# motorline.net
KiCad netlist of a schematic drawn in EAGLE
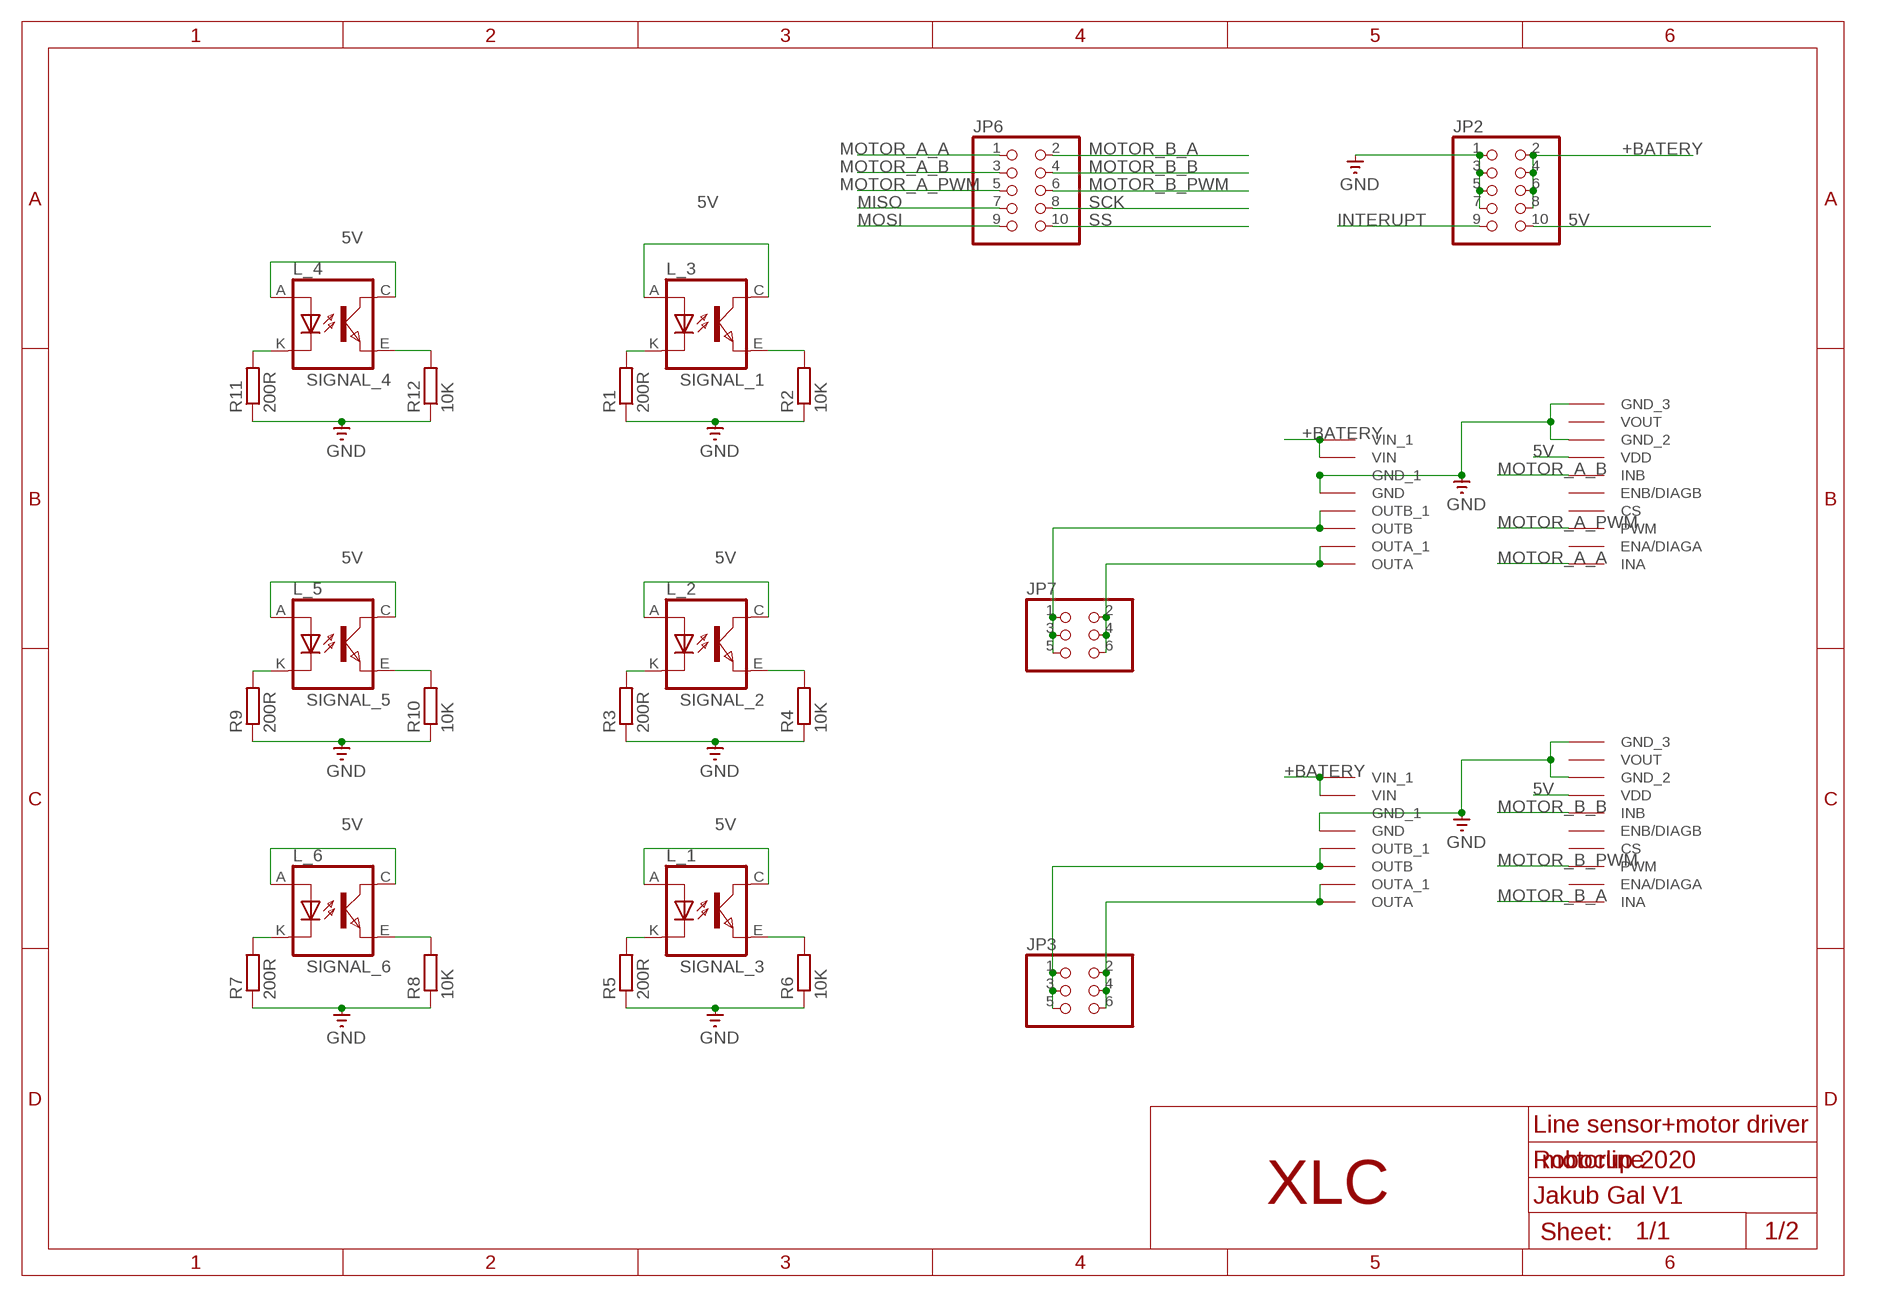
[diagram p0: schematic, sheet 1, part 1 of 2]
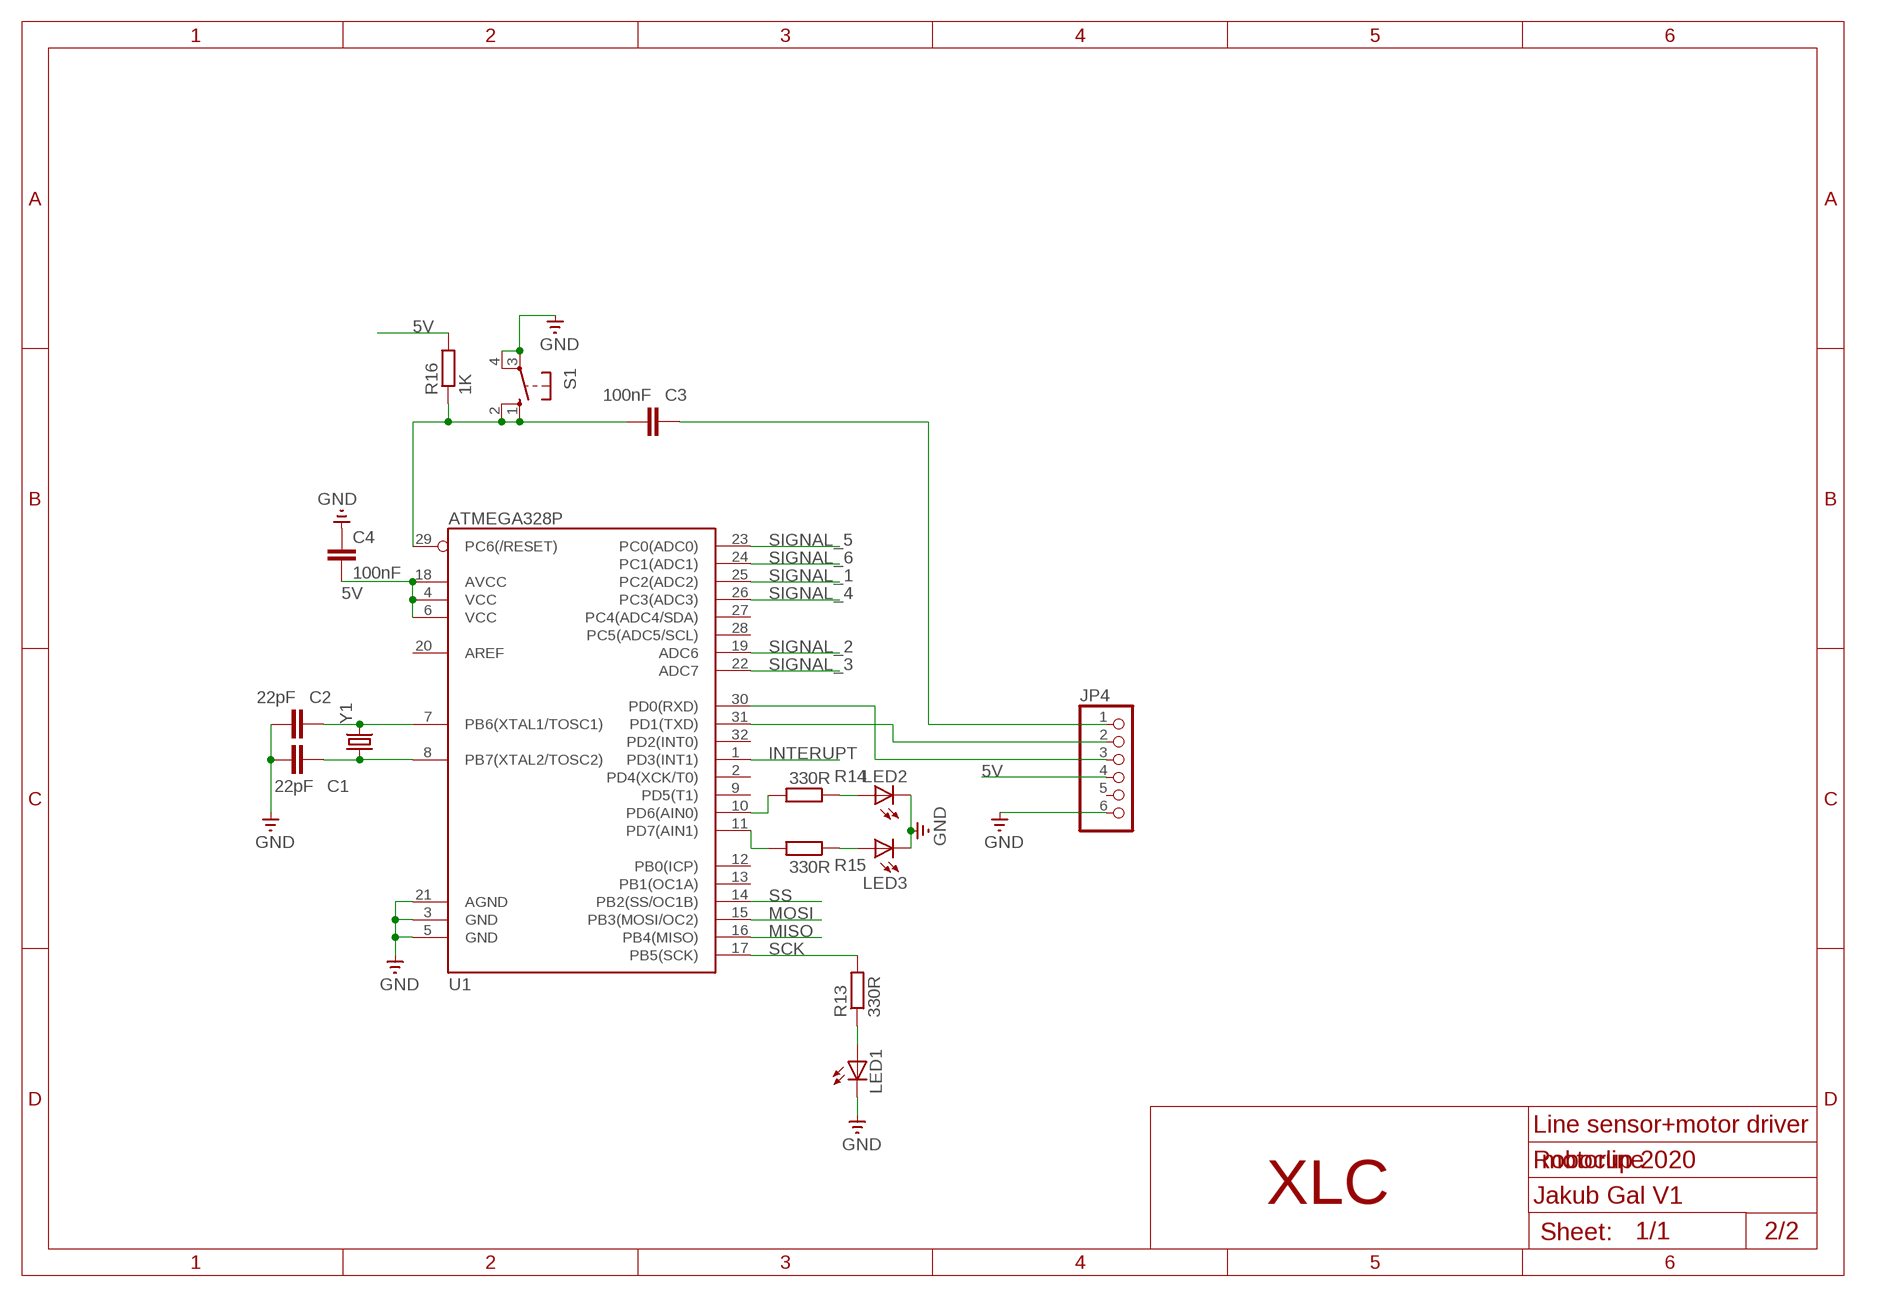
[diagram p1: schematic, sheet 1, part 2 of 2]

(export (version "E")
  (design (tool "Eeschema 10.0.6"))
  (components
    (comp (ref "C1")
      (value "22pF")
      (footprint "eagle-import:C0603")
      (libsource (lib "eagle-import") (part "C-EUC0603"))
    )
    (comp (ref "C2")
      (value "22pF")
      (footprint "eagle-import:C0603")
      (libsource (lib "eagle-import") (part "C-EUC0603"))
    )
    (comp (ref "C3")
      (value "100nF")
      (footprint "eagle-import:C0603")
      (libsource (lib "eagle-import") (part "C-EUC0603"))
    )
    (comp (ref "C4")
      (value "100nF")
      (footprint "eagle-import:C0603")
      (libsource (lib "eagle-import") (part "rcl_334_C-EUC0603"))
    )
    (comp (ref "JP2")
      (value "PINHD-2X5IDC")
      (footprint "eagle-import:2X05_IDC")
      (libsource (lib "eagle-import") (part "PINHD-2X5IDC"))
    )
    (comp (ref "JP3")
      (value "PINHD-2X3IDC")
      (footprint "eagle-import:2X03_IDC")
      (libsource (lib "eagle-import") (part "PINHD-2X3IDC"))
    )
    (comp (ref "JP4")
      (value "PINHD-1X6_2.54-90°")
      (footprint "eagle-import:1X06_90")
      (libsource (lib "eagle-import") (part "PINHD-1X6_2.54-90°"))
    )
    (comp (ref "JP6")
      (value "PINHD-2X5IDC")
      (footprint "eagle-import:2X05_IDC")
      (libsource (lib "eagle-import") (part "PINHD-2X5IDC"))
    )
    (comp (ref "JP7")
      (value "PINHD-2X3IDC")
      (footprint "eagle-import:2X03_IDC")
      (libsource (lib "eagle-import") (part "PINHD-2X3IDC"))
    )
    (comp (ref "LED1")
      (value "LEDCHIPLED_0603")
      (footprint "eagle-import:CHIPLED_0603")
      (libsource (lib "eagle-import") (part "LEDCHIPLED_0603"))
    )
    (comp (ref "LED2")
      (value "LEDCHIPLED_0603")
      (footprint "eagle-import:CHIPLED_0603")
      (libsource (lib "eagle-import") (part "LEDCHIPLED_0603"))
    )
    (comp (ref "LED3")
      (value "LEDCHIPLED_0603")
      (footprint "eagle-import:CHIPLED_0603")
      (libsource (lib "eagle-import") (part "LEDCHIPLED_0603"))
    )
    (comp (ref "L_1")
      (value "TCRT5000")
      (footprint "eagle-import:TCRT5000")
      (libsource (lib "eagle-import") (part "TCRT5000"))
    )
    (comp (ref "L_2")
      (value "TCRT5000")
      (footprint "eagle-import:TCRT5000")
      (libsource (lib "eagle-import") (part "TCRT5000"))
    )
    (comp (ref "L_3")
      (value "TCRT5000")
      (footprint "eagle-import:TCRT5000")
      (libsource (lib "eagle-import") (part "TCRT5000"))
    )
    (comp (ref "L_4")
      (value "TCRT5000")
      (footprint "eagle-import:TCRT5000")
      (fields (field (name "SPICEPREFIX") "O"))
      (libsource (lib "eagle-import") (part "TCRT5000"))
    )
    (comp (ref "L_5")
      (value "TCRT5000")
      (footprint "eagle-import:TCRT5000")
      (libsource (lib "eagle-import") (part "TCRT5000"))
    )
    (comp (ref "L_6")
      (value "TCRT5000")
      (footprint "eagle-import:TCRT5000")
      (fields (field (name "SPICEPREFIX") "O"))
      (libsource (lib "eagle-import") (part "TCRT5000"))
    )
    (comp (ref "R1")
      (value "200R")
      (footprint "eagle-import:R0603")
      (libsource (lib "eagle-import") (part "R-EU_R0603"))
    )
    (comp (ref "R2")
      (value "10K")
      (footprint "eagle-import:R0603")
      (libsource (lib "eagle-import") (part "R-EU_R0603"))
    )
    (comp (ref "R3")
      (value "200R")
      (footprint "eagle-import:R0603")
      (libsource (lib "eagle-import") (part "R-EU_R0603"))
    )
    (comp (ref "R4")
      (value "10K")
      (footprint "eagle-import:R0603")
      (libsource (lib "eagle-import") (part "R-EU_R0603"))
    )
    (comp (ref "R5")
      (value "200R")
      (footprint "eagle-import:R0603")
      (libsource (lib "eagle-import") (part "R-EU_R0603"))
    )
    (comp (ref "R6")
      (value "10K")
      (footprint "eagle-import:R0603")
      (libsource (lib "eagle-import") (part "R-EU_R0603"))
    )
    (comp (ref "R7")
      (value "200R")
      (footprint "eagle-import:R0603")
      (libsource (lib "eagle-import") (part "R-EU_R0603"))
    )
    (comp (ref "R8")
      (value "10K")
      (footprint "eagle-import:R0603")
      (libsource (lib "eagle-import") (part "R-EU_R0603"))
    )
    (comp (ref "R9")
      (value "200R")
      (footprint "eagle-import:R0603")
      (libsource (lib "eagle-import") (part "R-EU_R0603"))
    )
    (comp (ref "R10")
      (value "10K")
      (footprint "eagle-import:R0603")
      (libsource (lib "eagle-import") (part "R-EU_R0603"))
    )
    (comp (ref "R11")
      (value "200R")
      (footprint "eagle-import:R0603")
      (libsource (lib "eagle-import") (part "R-EU_R0603"))
    )
    (comp (ref "R12")
      (value "10K")
      (footprint "eagle-import:R0603")
      (libsource (lib "eagle-import") (part "R-EU_R0603"))
    )
    (comp (ref "R13")
      (value "330R")
      (footprint "eagle-import:R0603")
      (libsource (lib "eagle-import") (part "R-EU_R0603"))
    )
    (comp (ref "R14")
      (value "330R")
      (footprint "eagle-import:R0603")
      (libsource (lib "eagle-import") (part "R-EU_R0603"))
    )
    (comp (ref "R15")
      (value "330R")
      (footprint "eagle-import:R0603")
      (libsource (lib "eagle-import") (part "R-EU_R0603"))
    )
    (comp (ref "R16")
      (value "1K")
      (footprint "eagle-import:R0603")
      (libsource (lib "eagle-import") (part "R-EU_R0603"))
    )
    (comp (ref "S1")
      (value "10-XX")
      (footprint "eagle-import:B3F-10XX")
      (fields (field (name "MPN") "B3F-1000"))
      (libsource (lib "eagle-import") (part "10-XX"))
    )
    (comp (ref "U$1")
      (value "MOTOR_DRIVER")
      (footprint "eagle-import:MOTOR_DRIVER")
      (libsource (lib "eagle-import") (part "MOTOR_DRIVER"))
    )
    (comp (ref "U$2")
      (value "MOTOR_DRIVER")
      (footprint "eagle-import:MOTOR_DRIVER")
      (libsource (lib "eagle-import") (part "MOTOR_DRIVER"))
    )
    (comp (ref "U1")
      (value "ATMEGA328P")
      (footprint "eagle-import:TQFP32-08")
      (libsource (lib "eagle-import") (part "ATMEGA328_SMT"))
    )
    (comp (ref "Y1")
      (value "CRYSTALHC49US")
      (footprint "eagle-import:HC49US")
      (libsource (lib "eagle-import") (part "CRYSTALHC49US"))
    )
  )
  (nets
    (net (code "1") (name "/+BATERY") (class "Default")
      (node (ref "JP2") (pin "2") (pinfunction "2_2") (pintype "passive"))
      (node (ref "JP2") (pin "4") (pinfunction "4_4") (pintype "passive"))
      (node (ref "JP2") (pin "6") (pinfunction "6_6") (pintype "passive"))
      (node (ref "JP2") (pin "8") (pinfunction "8_8") (pintype "passive"))
      (node (ref "U$1") (pin "VIN") (pinfunction "VIN_VIN") (pintype "bidirectional"))
      (node (ref "U$1") (pin "VIN_1") (pinfunction "VIN_1_VIN_1") (pintype "bidirectional"))
      (node (ref "U$2") (pin "VIN") (pinfunction "VIN_VIN") (pintype "bidirectional"))
      (node (ref "U$2") (pin "VIN_1") (pinfunction "VIN_1_VIN_1") (pintype "bidirectional"))
    )
    (net (code "2") (name "/5V") (class "Default")
      (node (ref "C4") (pin "2") (pinfunction "2_2") (pintype "passive"))
      (node (ref "JP2") (pin "10") (pinfunction "10_10") (pintype "passive"))
      (node (ref "JP4") (pin "4") (pinfunction "4_4") (pintype "passive"))
      (node (ref "L_1") (pin "A") (pinfunction "ANODE_A") (pintype "passive"))
      (node (ref "L_1") (pin "C") (pinfunction "COLLECTOR_C") (pintype "passive"))
      (node (ref "L_2") (pin "A") (pinfunction "ANODE_A") (pintype "passive"))
      (node (ref "L_2") (pin "C") (pinfunction "COLLECTOR_C") (pintype "passive"))
      (node (ref "L_3") (pin "A") (pinfunction "ANODE_A") (pintype "passive"))
      (node (ref "L_3") (pin "C") (pinfunction "COLLECTOR_C") (pintype "passive"))
      (node (ref "L_4") (pin "A") (pinfunction "ANODE_A") (pintype "passive"))
      (node (ref "L_4") (pin "C") (pinfunction "COLLECTOR_C") (pintype "passive"))
      (node (ref "L_5") (pin "A") (pinfunction "ANODE_A") (pintype "passive"))
      (node (ref "L_5") (pin "C") (pinfunction "COLLECTOR_C") (pintype "passive"))
      (node (ref "L_6") (pin "A") (pinfunction "ANODE_A") (pintype "passive"))
      (node (ref "L_6") (pin "C") (pinfunction "COLLECTOR_C") (pintype "passive"))
      (node (ref "R16") (pin "2") (pinfunction "2_2") (pintype "passive"))
      (node (ref "U$1") (pin "VDD") (pinfunction "VDD_VDD") (pintype "bidirectional"))
      (node (ref "U$2") (pin "VDD") (pinfunction "VDD_VDD") (pintype "bidirectional"))
      (node (ref "U1") (pin "18") (pinfunction "AVCC_18") (pintype "bidirectional"))
      (node (ref "U1") (pin "4") (pinfunction "VCC_4") (pintype "bidirectional"))
      (node (ref "U1") (pin "6") (pinfunction "VCC_6") (pintype "bidirectional"))
    )
    (net (code "3") (name "/INTERUPT") (class "Default")
      (node (ref "JP2") (pin "9") (pinfunction "9_9") (pintype "passive"))
      (node (ref "U1") (pin "1") (pinfunction "PD3(INT1)_1") (pintype "bidirectional"))
    )
    (net (code "4") (name "/MISO") (class "Default")
      (node (ref "JP6") (pin "7") (pinfunction "7_7") (pintype "passive"))
      (node (ref "U1") (pin "16") (pinfunction "PB4(MISO)_16") (pintype "bidirectional"))
    )
    (net (code "5") (name "/MOSI") (class "Default")
      (node (ref "JP6") (pin "9") (pinfunction "9_9") (pintype "passive"))
      (node (ref "U1") (pin "15") (pinfunction "PB3(MOSI/OC2)_15") (pintype "bidirectional"))
    )
    (net (code "6") (name "/MOTOR_A_A") (class "Default")
      (node (ref "JP6") (pin "1") (pinfunction "1_1") (pintype "passive"))
      (node (ref "U$1") (pin "INA") (pinfunction "INA_INA") (pintype "bidirectional"))
    )
    (net (code "7") (name "/MOTOR_A_B") (class "Default")
      (node (ref "JP6") (pin "3") (pinfunction "3_3") (pintype "passive"))
      (node (ref "U$1") (pin "INB") (pinfunction "INB_INB") (pintype "bidirectional"))
    )
    (net (code "8") (name "/MOTOR_A_PWM") (class "Default")
      (node (ref "JP6") (pin "5") (pinfunction "5_5") (pintype "passive"))
      (node (ref "U$1") (pin "PWM") (pinfunction "PWM_PWM") (pintype "bidirectional"))
    )
    (net (code "9") (name "/MOTOR_B_A") (class "Default")
      (node (ref "JP6") (pin "2") (pinfunction "2_2") (pintype "passive"))
      (node (ref "U$2") (pin "INA") (pinfunction "INA_INA") (pintype "bidirectional"))
    )
    (net (code "10") (name "/MOTOR_B_B") (class "Default")
      (node (ref "JP6") (pin "4") (pinfunction "4_4") (pintype "passive"))
      (node (ref "U$2") (pin "INB") (pinfunction "INB_INB") (pintype "bidirectional"))
    )
    (net (code "11") (name "/MOTOR_B_PWM") (class "Default")
      (node (ref "JP6") (pin "6") (pinfunction "6_6") (pintype "passive"))
      (node (ref "U$2") (pin "PWM") (pinfunction "PWM_PWM") (pintype "bidirectional"))
    )
    (net (code "12") (name "/SCK") (class "Default")
      (node (ref "JP6") (pin "8") (pinfunction "8_8") (pintype "passive"))
      (node (ref "R13") (pin "2") (pinfunction "2_2") (pintype "passive"))
      (node (ref "U1") (pin "17") (pinfunction "PB5(SCK)_17") (pintype "bidirectional"))
    )
    (net (code "13") (name "/SIGNAL_1") (class "Default")
      (node (ref "L_3") (pin "E") (pinfunction "EMITTER_E") (pintype "passive"))
      (node (ref "R2") (pin "2") (pinfunction "2_2") (pintype "passive"))
      (node (ref "U1") (pin "25") (pinfunction "PC2(ADC2)_25") (pintype "bidirectional"))
    )
    (net (code "14") (name "/SIGNAL_2") (class "Default")
      (node (ref "L_2") (pin "E") (pinfunction "EMITTER_E") (pintype "passive"))
      (node (ref "R4") (pin "2") (pinfunction "2_2") (pintype "passive"))
      (node (ref "U1") (pin "19") (pinfunction "ADC6_19") (pintype "bidirectional"))
    )
    (net (code "15") (name "/SIGNAL_3") (class "Default")
      (node (ref "L_1") (pin "E") (pinfunction "EMITTER_E") (pintype "passive"))
      (node (ref "R6") (pin "2") (pinfunction "2_2") (pintype "passive"))
      (node (ref "U1") (pin "22") (pinfunction "ADC7_22") (pintype "bidirectional"))
    )
    (net (code "16") (name "/SIGNAL_4") (class "Default")
      (node (ref "L_4") (pin "E") (pinfunction "EMITTER_E") (pintype "passive"))
      (node (ref "R12") (pin "2") (pinfunction "2_2") (pintype "passive"))
      (node (ref "U1") (pin "26") (pinfunction "PC3(ADC3)_26") (pintype "bidirectional"))
    )
    (net (code "17") (name "/SIGNAL_5") (class "Default")
      (node (ref "L_5") (pin "E") (pinfunction "EMITTER_E") (pintype "passive"))
      (node (ref "R10") (pin "2") (pinfunction "2_2") (pintype "passive"))
      (node (ref "U1") (pin "23") (pinfunction "PC0(ADC0)_23") (pintype "bidirectional"))
    )
    (net (code "18") (name "/SIGNAL_6") (class "Default")
      (node (ref "L_6") (pin "E") (pinfunction "EMITTER_E") (pintype "passive"))
      (node (ref "R8") (pin "2") (pinfunction "2_2") (pintype "passive"))
      (node (ref "U1") (pin "24") (pinfunction "PC1(ADC1)_24") (pintype "bidirectional"))
    )
    (net (code "19") (name "/SS") (class "Default")
      (node (ref "JP6") (pin "10") (pinfunction "10_10") (pintype "passive"))
      (node (ref "U1") (pin "14") (pinfunction "PB2(SS/OC1B)_14") (pintype "bidirectional"))
    )
    (net (code "20") (name "GND") (class "Default")
      (node (ref "C1") (pin "1") (pinfunction "1_1") (pintype "passive"))
      (node (ref "C2") (pin "1") (pinfunction "1_1") (pintype "passive"))
      (node (ref "C4") (pin "1") (pinfunction "1_1") (pintype "passive"))
      (node (ref "JP2") (pin "1") (pinfunction "1_1") (pintype "passive"))
      (node (ref "JP2") (pin "3") (pinfunction "3_3") (pintype "passive"))
      (node (ref "JP2") (pin "5") (pinfunction "5_5") (pintype "passive"))
      (node (ref "JP2") (pin "7") (pinfunction "7_7") (pintype "passive"))
      (node (ref "JP4") (pin "6") (pinfunction "6_6") (pintype "passive"))
      (node (ref "LED1") (pin "C") (pinfunction "C_C") (pintype "passive"))
      (node (ref "LED2") (pin "C") (pinfunction "C_C") (pintype "passive"))
      (node (ref "LED3") (pin "C") (pinfunction "C_C") (pintype "passive"))
      (node (ref "R1") (pin "1") (pinfunction "1_1") (pintype "passive"))
      (node (ref "R10") (pin "1") (pinfunction "1_1") (pintype "passive"))
      (node (ref "R11") (pin "1") (pinfunction "1_1") (pintype "passive"))
      (node (ref "R12") (pin "1") (pinfunction "1_1") (pintype "passive"))
      (node (ref "R2") (pin "1") (pinfunction "1_1") (pintype "passive"))
      (node (ref "R3") (pin "1") (pinfunction "1_1") (pintype "passive"))
      (node (ref "R4") (pin "1") (pinfunction "1_1") (pintype "passive"))
      (node (ref "R5") (pin "1") (pinfunction "1_1") (pintype "passive"))
      (node (ref "R6") (pin "1") (pinfunction "1_1") (pintype "passive"))
      (node (ref "R7") (pin "1") (pinfunction "1_1") (pintype "passive"))
      (node (ref "R8") (pin "1") (pinfunction "1_1") (pintype "passive"))
      (node (ref "R9") (pin "1") (pinfunction "1_1") (pintype "passive"))
      (node (ref "S1") (pin "3") (pinfunction "P_3") (pintype "passive"))
      (node (ref "S1") (pin "4") (pinfunction "P1_4") (pintype "passive"))
      (node (ref "U$1") (pin "GND") (pinfunction "GND_GND") (pintype "bidirectional"))
      (node (ref "U$1") (pin "GND_1") (pinfunction "GND_1_GND_1") (pintype "bidirectional"))
      (node (ref "U$1") (pin "GND_2") (pinfunction "GND_2_GND_2") (pintype "bidirectional"))
      (node (ref "U$1") (pin "GND_3") (pinfunction "GND_3_GND_3") (pintype "bidirectional"))
      (node (ref "U$2") (pin "GND") (pinfunction "GND_GND") (pintype "bidirectional"))
      (node (ref "U$2") (pin "GND_1") (pinfunction "GND_1_GND_1") (pintype "bidirectional"))
      (node (ref "U$2") (pin "GND_2") (pinfunction "GND_2_GND_2") (pintype "bidirectional"))
      (node (ref "U$2") (pin "GND_3") (pinfunction "GND_3_GND_3") (pintype "bidirectional"))
      (node (ref "U1") (pin "21") (pinfunction "AGND_21") (pintype "bidirectional"))
      (node (ref "U1") (pin "3") (pinfunction "GND_3") (pintype "bidirectional"))
      (node (ref "U1") (pin "5") (pinfunction "GND_5") (pintype "bidirectional"))
    )
    (net (code "21") (name "Net-(C3-Pad2)") (class "Default")
      (node (ref "C3") (pin "2") (pinfunction "2_2") (pintype "passive"))
      (node (ref "JP4") (pin "1") (pinfunction "1_1") (pintype "passive"))
    )
    (net (code "22") (name "Net-(JP3-Pad1)") (class "Default")
      (node (ref "JP3") (pin "1") (pinfunction "1_1") (pintype "passive"))
      (node (ref "JP3") (pin "3") (pinfunction "3_3") (pintype "passive"))
      (node (ref "JP3") (pin "5") (pinfunction "5_5") (pintype "passive"))
      (node (ref "U$2") (pin "OUTB") (pinfunction "OUTB_OUTB") (pintype "bidirectional"))
      (node (ref "U$2") (pin "OUTB_1") (pinfunction "OUTB_1_OUTB_1") (pintype "bidirectional"))
    )
    (net (code "23") (name "Net-(JP3-Pad2)") (class "Default")
      (node (ref "JP3") (pin "2") (pinfunction "2_2") (pintype "passive"))
      (node (ref "JP3") (pin "4") (pinfunction "4_4") (pintype "passive"))
      (node (ref "JP3") (pin "6") (pinfunction "6_6") (pintype "passive"))
      (node (ref "U$2") (pin "OUTA") (pinfunction "OUTA_OUTA") (pintype "bidirectional"))
      (node (ref "U$2") (pin "OUTA_1") (pinfunction "OUTA_1_OUTA_1") (pintype "bidirectional"))
    )
    (net (code "24") (name "Net-(JP7-Pad1)") (class "Default")
      (node (ref "JP7") (pin "1") (pinfunction "1_1") (pintype "passive"))
      (node (ref "JP7") (pin "3") (pinfunction "3_3") (pintype "passive"))
      (node (ref "JP7") (pin "5") (pinfunction "5_5") (pintype "passive"))
      (node (ref "U$1") (pin "OUTB") (pinfunction "OUTB_OUTB") (pintype "bidirectional"))
      (node (ref "U$1") (pin "OUTB_1") (pinfunction "OUTB_1_OUTB_1") (pintype "bidirectional"))
    )
    (net (code "25") (name "Net-(JP7-Pad2)") (class "Default")
      (node (ref "JP7") (pin "2") (pinfunction "2_2") (pintype "passive"))
      (node (ref "JP7") (pin "4") (pinfunction "4_4") (pintype "passive"))
      (node (ref "JP7") (pin "6") (pinfunction "6_6") (pintype "passive"))
      (node (ref "U$1") (pin "OUTA") (pinfunction "OUTA_OUTA") (pintype "bidirectional"))
      (node (ref "U$1") (pin "OUTA_1") (pinfunction "OUTA_1_OUTA_1") (pintype "bidirectional"))
    )
    (net (code "26") (name "Net-(LED1-PadA)") (class "Default")
      (node (ref "LED1") (pin "A") (pinfunction "A_A") (pintype "passive"))
      (node (ref "R13") (pin "1") (pinfunction "1_1") (pintype "passive"))
    )
    (net (code "27") (name "Net-(LED2-PadA)") (class "Default")
      (node (ref "LED2") (pin "A") (pinfunction "A_A") (pintype "passive"))
      (node (ref "R14") (pin "1") (pinfunction "1_1") (pintype "passive"))
    )
    (net (code "28") (name "Net-(LED3-PadA)") (class "Default")
      (node (ref "LED3") (pin "A") (pinfunction "A_A") (pintype "passive"))
      (node (ref "R15") (pin "1") (pinfunction "1_1") (pintype "passive"))
    )
    (net (code "29") (name "Net-(L_1-CATHODE)") (class "Default")
      (node (ref "L_1") (pin "K") (pinfunction "CATHODE_K") (pintype "passive"))
      (node (ref "R5") (pin "2") (pinfunction "2_2") (pintype "passive"))
    )
    (net (code "30") (name "Net-(L_2-CATHODE)") (class "Default")
      (node (ref "L_2") (pin "K") (pinfunction "CATHODE_K") (pintype "passive"))
      (node (ref "R3") (pin "2") (pinfunction "2_2") (pintype "passive"))
    )
    (net (code "31") (name "Net-(L_3-CATHODE)") (class "Default")
      (node (ref "L_3") (pin "K") (pinfunction "CATHODE_K") (pintype "passive"))
      (node (ref "R1") (pin "2") (pinfunction "2_2") (pintype "passive"))
    )
    (net (code "32") (name "Net-(L_4-CATHODE)") (class "Default")
      (node (ref "L_4") (pin "K") (pinfunction "CATHODE_K") (pintype "passive"))
      (node (ref "R11") (pin "2") (pinfunction "2_2") (pintype "passive"))
    )
    (net (code "33") (name "Net-(L_5-CATHODE)") (class "Default")
      (node (ref "L_5") (pin "K") (pinfunction "CATHODE_K") (pintype "passive"))
      (node (ref "R9") (pin "2") (pinfunction "2_2") (pintype "passive"))
    )
    (net (code "34") (name "Net-(L_6-CATHODE)") (class "Default")
      (node (ref "L_6") (pin "K") (pinfunction "CATHODE_K") (pintype "passive"))
      (node (ref "R7") (pin "2") (pinfunction "2_2") (pintype "passive"))
    )
    (net (code "35") (name "Net-(S1-S)") (class "Default")
      (node (ref "C3") (pin "1") (pinfunction "1_1") (pintype "passive"))
      (node (ref "R16") (pin "1") (pinfunction "1_1") (pintype "passive"))
      (node (ref "S1") (pin "1") (pinfunction "S_1") (pintype "passive"))
      (node (ref "S1") (pin "2") (pinfunction "S1_2") (pintype "passive"))
      (node (ref "U1") (pin "29") (pinfunction "PC6(/RESET)_29") (pintype "bidirectional"))
    )
    (net (code "36") (name "Net-(U1-PB6(XTAL1{slash}TOSC1))") (class "Default")
      (node (ref "C2") (pin "2") (pinfunction "2_2") (pintype "passive"))
      (node (ref "U1") (pin "7") (pinfunction "PB6(XTAL1/TOSC1)_7") (pintype "bidirectional"))
      (node (ref "Y1") (pin "2") (pinfunction "2_2") (pintype "passive"))
    )
    (net (code "37") (name "Net-(U1-PB7(XTAL2{slash}TOSC2))") (class "Default")
      (node (ref "C1") (pin "2") (pinfunction "2_2") (pintype "passive"))
      (node (ref "U1") (pin "8") (pinfunction "PB7(XTAL2/TOSC2)_8") (pintype "bidirectional"))
      (node (ref "Y1") (pin "1") (pinfunction "1_1") (pintype "passive"))
    )
    (net (code "38") (name "Net-(U1-PD0(RXD))") (class "Default")
      (node (ref "JP4") (pin "3") (pinfunction "3_3") (pintype "passive"))
      (node (ref "U1") (pin "30") (pinfunction "PD0(RXD)_30") (pintype "bidirectional"))
    )
    (net (code "39") (name "Net-(U1-PD1(TXD))") (class "Default")
      (node (ref "JP4") (pin "2") (pinfunction "2_2") (pintype "passive"))
      (node (ref "U1") (pin "31") (pinfunction "PD1(TXD)_31") (pintype "bidirectional"))
    )
    (net (code "40") (name "Net-(U1-PD6(AIN0))") (class "Default")
      (node (ref "R14") (pin "2") (pinfunction "2_2") (pintype "passive"))
      (node (ref "U1") (pin "10") (pinfunction "PD6(AIN0)_10") (pintype "bidirectional"))
    )
    (net (code "41") (name "Net-(U1-PD7(AIN1))") (class "Default")
      (node (ref "R15") (pin "2") (pinfunction "2_2") (pintype "passive"))
      (node (ref "U1") (pin "11") (pinfunction "PD7(AIN1)_11") (pintype "bidirectional"))
    )
    (net (code "42") (name "unconnected-(JP4-Pad5)") (class "Default")
      (node (ref "JP4") (pin "5") (pinfunction "5_5") (pintype "passive"))
    )
    (net (code "43") (name "unconnected-(U$1-PadCS)") (class "Default")
      (node (ref "U$1") (pin "CS") (pinfunction "CS_CS") (pintype "bidirectional"))
    )
    (net (code "44") (name "unconnected-(U$1-PadENA{slash}DIAGA)") (class "Default")
      (node (ref "U$1") (pin "ENA/DIAGA") (pinfunction "ENA/DIAGA_ENA/DIAGA") (pintype "bidirectional"))
    )
    (net (code "45") (name "unconnected-(U$1-PadENB{slash}DIAGB)") (class "Default")
      (node (ref "U$1") (pin "ENB/DIAGB") (pinfunction "ENB/DIAGB_ENB/DIAGB") (pintype "bidirectional"))
    )
    (net (code "46") (name "unconnected-(U$1-PadVOUT)") (class "Default")
      (node (ref "U$1") (pin "VOUT") (pinfunction "VOUT_VOUT") (pintype "bidirectional"))
    )
    (net (code "47") (name "unconnected-(U$2-PadCS)") (class "Default")
      (node (ref "U$2") (pin "CS") (pinfunction "CS_CS") (pintype "bidirectional"))
    )
    (net (code "48") (name "unconnected-(U$2-PadENA{slash}DIAGA)") (class "Default")
      (node (ref "U$2") (pin "ENA/DIAGA") (pinfunction "ENA/DIAGA_ENA/DIAGA") (pintype "bidirectional"))
    )
    (net (code "49") (name "unconnected-(U$2-PadENB{slash}DIAGB)") (class "Default")
      (node (ref "U$2") (pin "ENB/DIAGB") (pinfunction "ENB/DIAGB_ENB/DIAGB") (pintype "bidirectional"))
    )
    (net (code "50") (name "unconnected-(U$2-PadVOUT)") (class "Default")
      (node (ref "U$2") (pin "VOUT") (pinfunction "VOUT_VOUT") (pintype "bidirectional"))
    )
    (net (code "51") (name "unconnected-(U1-AREF-Pad20)") (class "Default")
      (node (ref "U1") (pin "20") (pinfunction "AREF_20") (pintype "bidirectional"))
    )
    (net (code "52") (name "unconnected-(U1-PB0(ICP)-Pad12)") (class "Default")
      (node (ref "U1") (pin "12") (pinfunction "PB0(ICP)_12") (pintype "bidirectional"))
    )
    (net (code "53") (name "unconnected-(U1-PB1(OC1A)-Pad13)") (class "Default")
      (node (ref "U1") (pin "13") (pinfunction "PB1(OC1A)_13") (pintype "bidirectional"))
    )
    (net (code "54") (name "unconnected-(U1-PC4(ADC4{slash}SDA)-Pad27)") (class "Default")
      (node (ref "U1") (pin "27") (pinfunction "PC4(ADC4/SDA)_27") (pintype "bidirectional"))
    )
    (net (code "55") (name "unconnected-(U1-PC5(ADC5{slash}SCL)-Pad28)") (class "Default")
      (node (ref "U1") (pin "28") (pinfunction "PC5(ADC5/SCL)_28") (pintype "bidirectional"))
    )
    (net (code "56") (name "unconnected-(U1-PD2(INT0)-Pad32)") (class "Default")
      (node (ref "U1") (pin "32") (pinfunction "PD2(INT0)_32") (pintype "bidirectional"))
    )
    (net (code "57") (name "unconnected-(U1-PD4(XCK{slash}T0)-Pad2)") (class "Default")
      (node (ref "U1") (pin "2") (pinfunction "PD4(XCK/T0)_2") (pintype "bidirectional"))
    )
    (net (code "58") (name "unconnected-(U1-PD5(T1)-Pad9)") (class "Default")
      (node (ref "U1") (pin "9") (pinfunction "PD5(T1)_9") (pintype "bidirectional"))
    )
  )
)
